# Cyllene.net
KiCad netlist of a schematic drawn in EAGLE
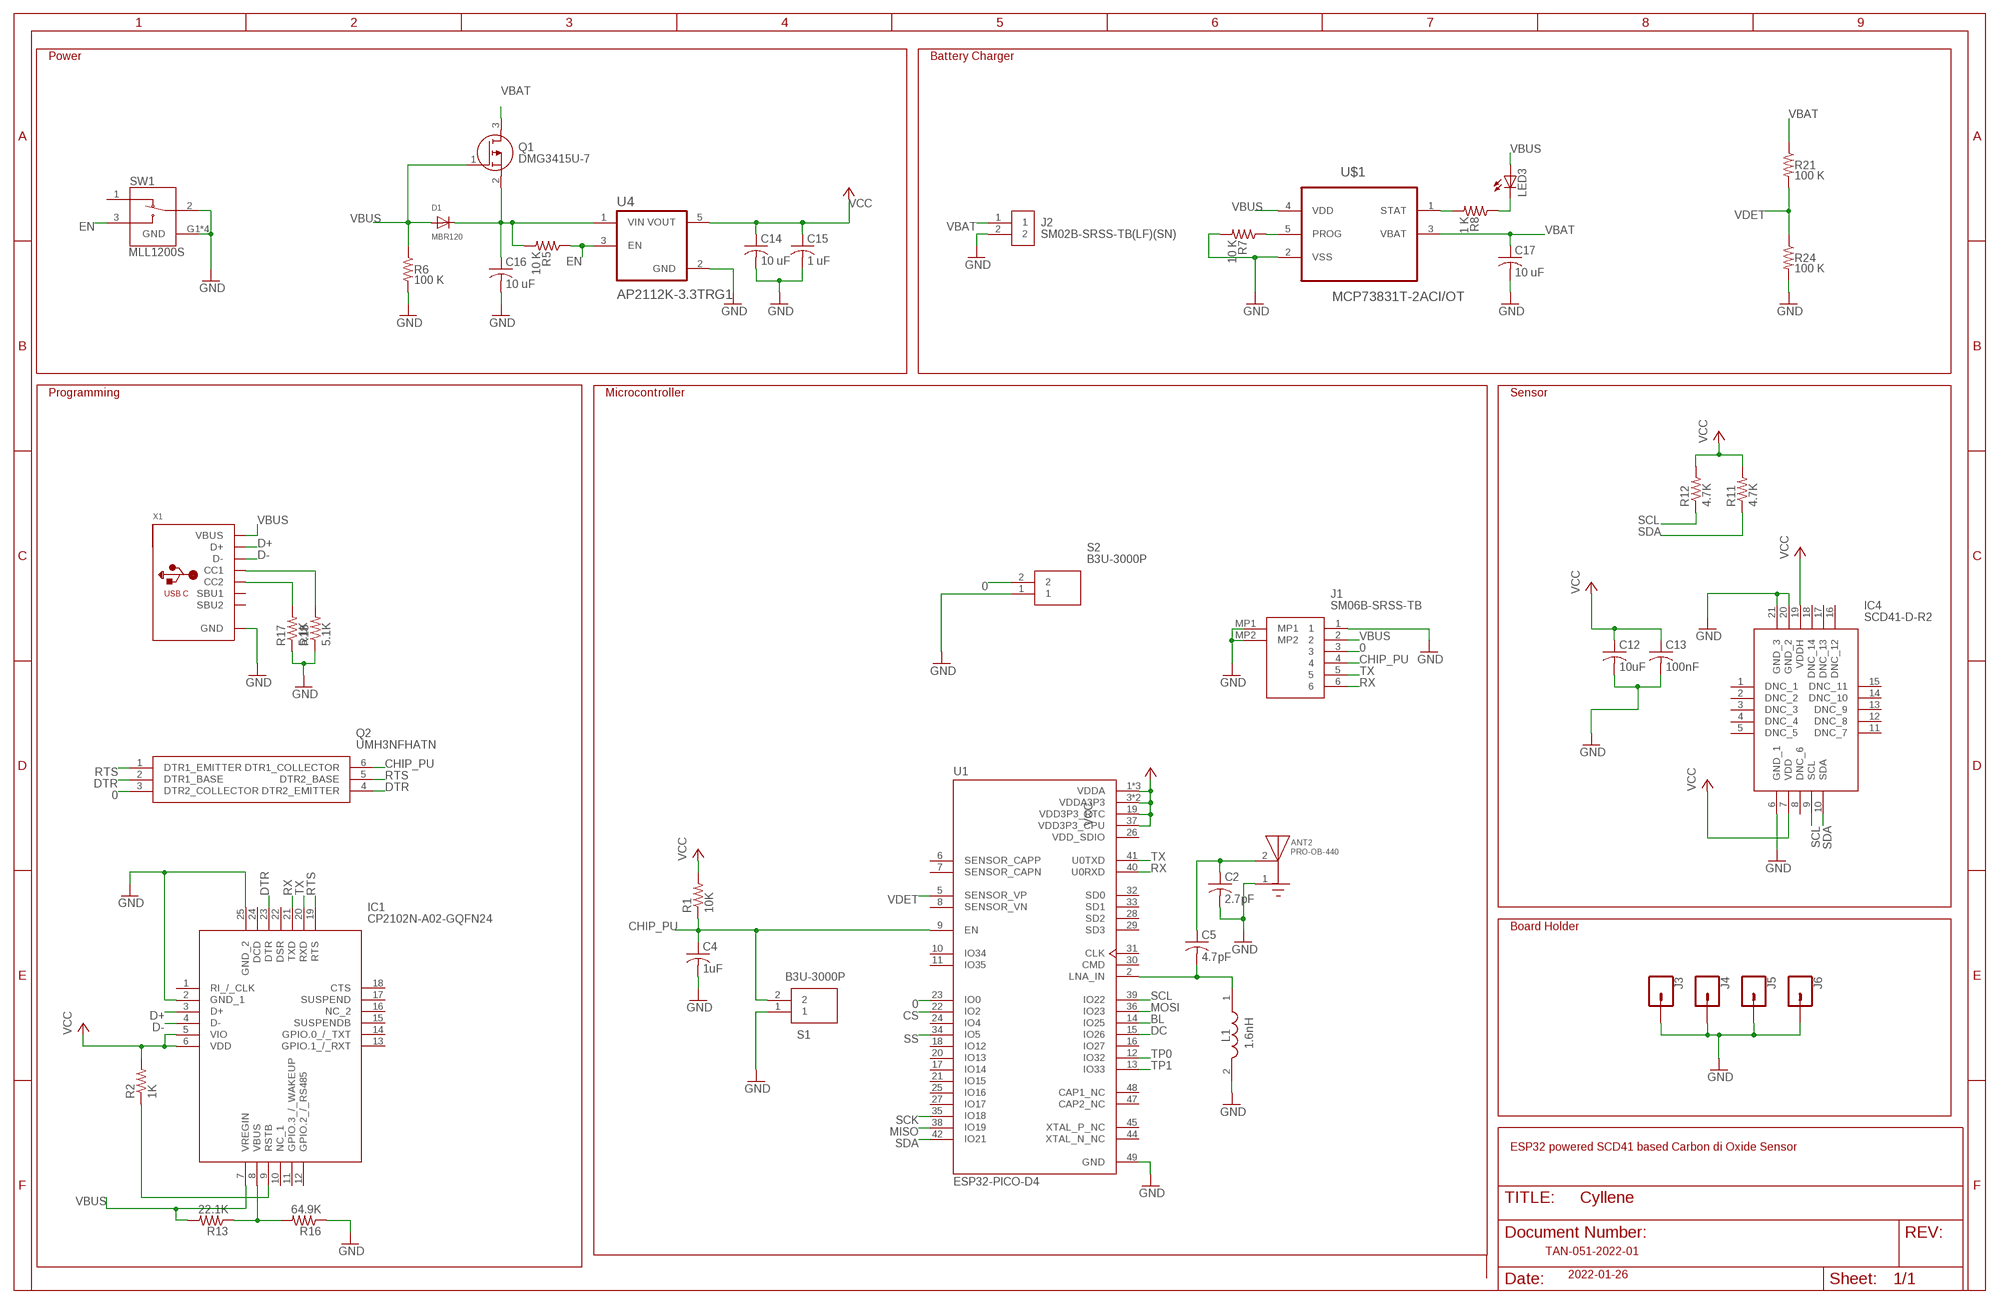
[diagram p0: schematic, sheet 1]

(export (version "E")
  (design (tool "Eeschema 10.0.6"))
  (components
    (comp (ref "ANT2")
      (value "PRO-OB-440")
      (footprint "eagle-import:ANT_PRO-OB-440")
      (fields (field (name "MF") "Proant AB"))
      (libsource (lib "eagle-import") (part "PRO-OB-440"))
    )
    (comp (ref "C2")
      (value "2.7pF")
      (footprint "eagle-import:C0402")
      (libsource (lib "eagle-import") (part "C-USC0402"))
    )
    (comp (ref "C4")
      (value "1uF")
      (footprint "eagle-import:C0402")
      (libsource (lib "eagle-import") (part "C-USC0402"))
    )
    (comp (ref "C5")
      (value "4.7pF")
      (footprint "eagle-import:C0402")
      (libsource (lib "eagle-import") (part "C-USC0402"))
    )
    (comp (ref "C12")
      (value "10uF")
      (footprint "eagle-import:C0402")
      (libsource (lib "eagle-import") (part "C-USC0402"))
    )
    (comp (ref "C13")
      (value "100nF")
      (footprint "eagle-import:C0402")
      (libsource (lib "eagle-import") (part "C-USC0402"))
    )
    (comp (ref "C14")
      (value "10 uF")
      (footprint "eagle-import:C0402")
      (libsource (lib "eagle-import") (part "C-USC0402"))
    )
    (comp (ref "C15")
      (value "1 uF")
      (footprint "eagle-import:C0402")
      (libsource (lib "eagle-import") (part "C-USC0402"))
    )
    (comp (ref "C16")
      (value "10 uF")
      (footprint "eagle-import:C0402")
      (libsource (lib "eagle-import") (part "C-USC0402"))
    )
    (comp (ref "C17")
      (value "10 uF")
      (footprint "eagle-import:C0402")
      (libsource (lib "eagle-import") (part "C-USC0402"))
    )
    (comp (ref "D1")
      (value "MBR120")
      (footprint "eagle-import:SOD-123")
      (libsource (lib "eagle-import") (part "DIODESOD-123"))
    )
    (comp (ref "IC1")
      (value "CP2102N-A02-GQFN24")
      (footprint "eagle-import:QFN50P400X400X80-25N")
      (fields (field (name "MOUSER_PART_NUMBER") "634-CP2102NA02GQFN24"))
      (libsource (lib "eagle-import") (part "CP2102N-A02-GQFN24"))
    )
    (comp (ref "IC4")
      (value "SCD41-D-R2")
      (footprint "eagle-import:SCD41DR2")
      (fields (field (name "MOUSER_PART_NUMBER") "403-SCD41-D-R2"))
      (libsource (lib "eagle-import") (part "SCD41-D-R2"))
    )
    (comp (ref "J1")
      (value "SM06B-SRSS-TB")
      (footprint "eagle-import:SM06BSRSSTB")
      (libsource (lib "eagle-import") (part "SM06B-SRSS-TB"))
    )
    (comp (ref "J2")
      (value "SM02B-SRSS-TB(LF)(SN)")
      (footprint "eagle-import:SM02B-SRSS-TB(LF)(SN)")
      (fields (field (name "MF") "JST Sales"))
      (libsource (lib "eagle-import") (part "SM02B-SRSS-TB(LF)(SN)"))
    )
    (comp (ref "J3")
      (value "CONN_01PTH_2MM")
      (footprint "eagle-import:1X01_2MM")
      (libsource (lib "eagle-import") (part "CONN_01PTH_2MM"))
    )
    (comp (ref "J4")
      (value "CONN_01PTH_2MM")
      (footprint "eagle-import:1X01_2MM")
      (libsource (lib "eagle-import") (part "CONN_01PTH_2MM"))
    )
    (comp (ref "J5")
      (value "CONN_01PTH_2MM")
      (footprint "eagle-import:1X01_2MM")
      (libsource (lib "eagle-import") (part "CONN_01PTH_2MM"))
    )
    (comp (ref "J6")
      (value "CONN_01PTH_2MM")
      (footprint "eagle-import:1X01_2MM")
      (libsource (lib "eagle-import") (part "CONN_01PTH_2MM"))
    )
    (comp (ref "L1")
      (value "1.6nH")
      (footprint "eagle-import:LQW15CNR20J00B")
      (fields
        (field (name "MANUFACTURER_PART_NUMBER") "LQG15WZ1N6C02D")
        (field (name "MOUSER_PART_NUMBER") "81-LQG15WZ1N6C02D")
      )
      (libsource (lib "eagle-import") (part "LQG15WZ1N6C02D"))
    )
    (comp (ref "LED3")
      (value "LEDCHIPLED_0603")
      (footprint "eagle-import:CHIPLED_0603")
      (libsource (lib "eagle-import") (part "LEDCHIPLED_0603"))
    )
    (comp (ref "Q1")
      (value "DMG3415U-7")
      (footprint "eagle-import:SOT96P240X100-3N")
      (fields (field (name "LCSC_PART_NUMBER") "C96616"))
      (libsource (lib "eagle-import") (part "DMG3415U-7"))
    )
    (comp (ref "Q2")
      (value "UMH3NFHATN")
      (footprint "eagle-import:SOT65P210X100-6N")
      (fields (field (name "MOUSER_PART_NUMBER") "755-UMH3NFHATN"))
      (libsource (lib "eagle-import") (part "UMH3NFHATN"))
    )
    (comp (ref "R1")
      (value "10K")
      (footprint "eagle-import:R0402")
      (libsource (lib "eagle-import") (part "R-US_R0402"))
    )
    (comp (ref "R2")
      (value "1K")
      (footprint "eagle-import:R0402")
      (libsource (lib "eagle-import") (part "R-US_R0402"))
    )
    (comp (ref "R5")
      (value "10 K")
      (footprint "eagle-import:R0402")
      (libsource (lib "eagle-import") (part "R-US_R0402"))
    )
    (comp (ref "R6")
      (value "100 K")
      (footprint "eagle-import:R0402")
      (libsource (lib "eagle-import") (part "R-US_R0402"))
    )
    (comp (ref "R7")
      (value "10 K")
      (footprint "eagle-import:R0402")
      (libsource (lib "eagle-import") (part "R-US_R0402"))
    )
    (comp (ref "R8")
      (value "1 K")
      (footprint "eagle-import:R0402")
      (libsource (lib "eagle-import") (part "R-US_R0402"))
    )
    (comp (ref "R11")
      (value "4.7K")
      (footprint "eagle-import:R0402")
      (libsource (lib "eagle-import") (part "R-US_R0402"))
    )
    (comp (ref "R12")
      (value "4.7K")
      (footprint "eagle-import:R0402")
      (libsource (lib "eagle-import") (part "R-US_R0402"))
    )
    (comp (ref "R13")
      (value "22.1K")
      (footprint "eagle-import:R0402")
      (libsource (lib "eagle-import") (part "R-US_R0402"))
    )
    (comp (ref "R16")
      (value "64.9K")
      (footprint "eagle-import:R0402")
      (libsource (lib "eagle-import") (part "R-US_R0402"))
    )
    (comp (ref "R17")
      (value "5.1K")
      (footprint "eagle-import:R0402")
      (libsource (lib "eagle-import") (part "R-US_R0402"))
    )
    (comp (ref "R18")
      (value "5.1K")
      (footprint "eagle-import:R0402")
      (libsource (lib "eagle-import") (part "R-US_R0402"))
    )
    (comp (ref "R21")
      (value "100 K")
      (footprint "eagle-import:R0402")
      (libsource (lib "eagle-import") (part "R-US_R0402"))
    )
    (comp (ref "R24")
      (value "100 K")
      (footprint "eagle-import:R0402")
      (libsource (lib "eagle-import") (part "R-US_R0402"))
    )
    (comp (ref "S1")
      (value "B3U-3000P")
      (footprint "eagle-import:B3U-1000P")
      (fields (field (name "MOUSER_PART_NUMBER") "653-B3U-3000P"))
      (libsource (lib "eagle-import") (part "B3U-3000P"))
    )
    (comp (ref "S2")
      (value "B3U-3000P")
      (footprint "eagle-import:B3U-1000P")
      (fields (field (name "MOUSER_PART_NUMBER") "653-B3U-3000P"))
      (libsource (lib "eagle-import") (part "B3U-3000P"))
    )
    (comp (ref "SW1")
      (value "MLL1200S")
      (footprint "eagle-import:SW_MLL1200S")
      (fields (field (name "COMMENT") "1437575-1") (field (name "MF") "TE Connectivity"))
      (libsource (lib "eagle-import") (part "MLL1200S"))
    )
    (comp (ref "U$1")
      (value "MCP73831T-2ACI/OT")
      (footprint "eagle-import:SOT95P280X145-5N")
      (fields (field (name "MF") "Microchip"))
      (libsource (lib "eagle-import") (part "MCP73831T-2ACI/OT"))
    )
    (comp (ref "U1")
      (value "ESP32-PICO-D4")
      (footprint "eagle-import:PQFN50P700X700X104-49N")
      (fields (field (name "MF") "Espressif Systems"))
      (libsource (lib "eagle-import") (part "ESP32-PICO-D4"))
    )
    (comp (ref "U4")
      (value "AP2112K-3.3TRG1")
      (footprint "eagle-import:SOT95P285X140-5N")
      (fields (field (name "MF") "Diodes Inc."))
      (libsource (lib "eagle-import") (part "AP2112K-3.3TRG1"))
    )
    (comp (ref "X1")
      (value "MICROBUILDER_USB_C")
      (footprint "eagle-import:MICROBUILDER_USB_C_CUSB31-CFM2AX-01-X")
      (libsource (lib "eagle-import") (part "MICROBUILDER_USB_C"))
    )
  )
  (nets
    (net (code "1") (name "/0") (class "Default")
      (node (ref "J1") (pin "3") (pinfunction "3_3") (pintype "bidirectional"))
      (node (ref "Q2") (pin "3") (pinfunction "DTR2_COLLECTOR_3") (pintype "bidirectional"))
      (node (ref "S2") (pin "2") (pinfunction "2_2") (pintype "bidirectional"))
      (node (ref "U1") (pin "23") (pinfunction "IO0_23") (pintype "bidirectional"))
    )
    (net (code "2") (name "/BL") (class "Default")
      (node (ref "U1") (pin "14") (pinfunction "IO25_14") (pintype "bidirectional"))
    )
    (net (code "3") (name "/CHIP_PU") (class "Default")
      (node (ref "C4") (pin "1") (pinfunction "1_1") (pintype "passive"))
      (node (ref "J1") (pin "4") (pinfunction "4_4") (pintype "bidirectional"))
      (node (ref "Q2") (pin "6") (pinfunction "DTR1_COLLECTOR_6") (pintype "bidirectional"))
      (node (ref "R1") (pin "1") (pinfunction "1_1") (pintype "passive"))
      (node (ref "S1") (pin "2") (pinfunction "2_2") (pintype "bidirectional"))
      (node (ref "U1") (pin "9") (pinfunction "EN_9") (pintype "input"))
    )
    (net (code "4") (name "/CS") (class "Default")
      (node (ref "U1") (pin "22") (pinfunction "IO2_22") (pintype "bidirectional"))
    )
    (net (code "5") (name "/D+") (class "Default")
      (node (ref "IC1") (pin "3") (pinfunction "D+_3") (pintype "bidirectional"))
      (node (ref "X1") (pin "A6") (pinfunction "D+_A6") (pintype "bidirectional"))
      (node (ref "X1") (pin "B6") (pinfunction "D+_B6") (pintype "bidirectional"))
    )
    (net (code "6") (name "/D-") (class "Default")
      (node (ref "IC1") (pin "4") (pinfunction "D-_4") (pintype "bidirectional"))
      (node (ref "X1") (pin "A7") (pinfunction "D-_A7") (pintype "bidirectional"))
      (node (ref "X1") (pin "B7") (pinfunction "D-_B7") (pintype "bidirectional"))
    )
    (net (code "7") (name "/DC") (class "Default")
      (node (ref "U1") (pin "15") (pinfunction "IO26_15") (pintype "bidirectional"))
    )
    (net (code "8") (name "/DTR") (class "Default")
      (node (ref "IC1") (pin "23") (pinfunction "DTR_23") (pintype "bidirectional"))
      (node (ref "Q2") (pin "2") (pinfunction "DTR1_BASE_2") (pintype "bidirectional"))
      (node (ref "Q2") (pin "4") (pinfunction "DTR2_EMITTER_4") (pintype "bidirectional"))
    )
    (net (code "9") (name "/EN") (class "Default")
      (node (ref "R5") (pin "1") (pinfunction "1_1") (pintype "passive"))
      (node (ref "SW1") (pin "3") (pinfunction "3_3") (pintype "passive"))
      (node (ref "U4") (pin "3") (pinfunction "EN_3") (pintype "input"))
    )
    (net (code "10") (name "/MISO") (class "Default")
      (node (ref "U1") (pin "38") (pinfunction "IO19_38") (pintype "bidirectional"))
    )
    (net (code "11") (name "/MOSI") (class "Default")
      (node (ref "U1") (pin "36") (pinfunction "IO23_36") (pintype "bidirectional"))
    )
    (net (code "12") (name "/RTS") (class "Default")
      (node (ref "IC1") (pin "19") (pinfunction "RTS_19") (pintype "bidirectional"))
      (node (ref "Q2") (pin "1") (pinfunction "DTR1_EMITTER_1") (pintype "bidirectional"))
      (node (ref "Q2") (pin "5") (pinfunction "DTR2_BASE_5") (pintype "bidirectional"))
    )
    (net (code "13") (name "/RX") (class "Default")
      (node (ref "IC1") (pin "21") (pinfunction "TXD_21") (pintype "bidirectional"))
      (node (ref "J1") (pin "6") (pinfunction "6_6") (pintype "bidirectional"))
      (node (ref "U1") (pin "40") (pinfunction "U0RXD_40") (pintype "bidirectional"))
    )
    (net (code "14") (name "/SCK") (class "Default")
      (node (ref "U1") (pin "35") (pinfunction "IO18_35") (pintype "bidirectional"))
    )
    (net (code "15") (name "/SCL") (class "Default")
      (node (ref "IC4") (pin "9") (pinfunction "SCL_9") (pintype "bidirectional"))
      (node (ref "R12") (pin "1") (pinfunction "1_1") (pintype "passive"))
      (node (ref "U1") (pin "39") (pinfunction "IO22_39") (pintype "bidirectional"))
    )
    (net (code "16") (name "/SDA") (class "Default")
      (node (ref "IC4") (pin "10") (pinfunction "SDA_10") (pintype "bidirectional"))
      (node (ref "R11") (pin "1") (pinfunction "1_1") (pintype "passive"))
      (node (ref "U1") (pin "42") (pinfunction "IO21_42") (pintype "bidirectional"))
    )
    (net (code "17") (name "/SS") (class "Default")
      (node (ref "U1") (pin "34") (pinfunction "IO5_34") (pintype "bidirectional"))
    )
    (net (code "18") (name "/TP0") (class "Default")
      (node (ref "U1") (pin "12") (pinfunction "IO32_12") (pintype "bidirectional"))
    )
    (net (code "19") (name "/TP1") (class "Default")
      (node (ref "U1") (pin "13") (pinfunction "IO33_13") (pintype "bidirectional"))
    )
    (net (code "20") (name "/TX") (class "Default")
      (node (ref "IC1") (pin "20") (pinfunction "RXD_20") (pintype "bidirectional"))
      (node (ref "J1") (pin "5") (pinfunction "5_5") (pintype "bidirectional"))
      (node (ref "U1") (pin "41") (pinfunction "U0TXD_41") (pintype "bidirectional"))
    )
    (net (code "21") (name "/VBAT") (class "Default")
      (node (ref "C17") (pin "1") (pinfunction "1_1") (pintype "passive"))
      (node (ref "J2") (pin "1") (pinfunction "1_1") (pintype "bidirectional"))
      (node (ref "Q1") (pin "3") (pinfunction "D_3") (pintype "bidirectional"))
      (node (ref "R21") (pin "1") (pinfunction "1_1") (pintype "passive"))
      (node (ref "U$1") (pin "3") (pinfunction "VBAT_3") (pintype "output"))
    )
    (net (code "22") (name "/VBUS") (class "Default")
      (node (ref "D1") (pin "A") (pinfunction "A_A") (pintype "passive"))
      (node (ref "IC1") (pin "7") (pinfunction "VREGIN_7") (pintype "bidirectional"))
      (node (ref "J1") (pin "2") (pinfunction "2_2") (pintype "bidirectional"))
      (node (ref "LED3") (pin "A") (pinfunction "A_A") (pintype "passive"))
      (node (ref "Q1") (pin "1") (pinfunction "G_1") (pintype "bidirectional"))
      (node (ref "R13") (pin "2") (pinfunction "2_2") (pintype "passive"))
      (node (ref "R6") (pin "1") (pinfunction "1_1") (pintype "passive"))
      (node (ref "U$1") (pin "4") (pinfunction "VDD_4") (pintype "power_in"))
      (node (ref "X1") (pin "A4B9") (pinfunction "VBUS_A4B9") (pintype "power_in"))
      (node (ref "X1") (pin "B4A9") (pinfunction "VBUS_B4A9") (pintype "power_in"))
    )
    (net (code "23") (name "/VDD_SDIO") (class "Default")
      (node (ref "U1") (pin "26") (pinfunction "VDD_SDIO_26") (pintype "power_in"))
    )
    (net (code "24") (name "/VDET") (class "Default")
      (node (ref "R21") (pin "2") (pinfunction "2_2") (pintype "passive"))
      (node (ref "R24") (pin "1") (pinfunction "1_1") (pintype "passive"))
      (node (ref "U1") (pin "5") (pinfunction "SENSOR_VP_5") (pintype "input"))
    )
    (net (code "25") (name "GND") (class "Default")
      (node (ref "ANT2") (pin "1") (pinfunction "GND_1") (pintype "power_in"))
      (node (ref "C12") (pin "2") (pinfunction "2_2") (pintype "passive"))
      (node (ref "C13") (pin "2") (pinfunction "2_2") (pintype "passive"))
      (node (ref "C14") (pin "2") (pinfunction "2_2") (pintype "passive"))
      (node (ref "C15") (pin "2") (pinfunction "2_2") (pintype "passive"))
      (node (ref "C16") (pin "2") (pinfunction "2_2") (pintype "passive"))
      (node (ref "C17") (pin "2") (pinfunction "2_2") (pintype "passive"))
      (node (ref "C2") (pin "2") (pinfunction "2_2") (pintype "passive"))
      (node (ref "C4") (pin "2") (pinfunction "2_2") (pintype "passive"))
      (node (ref "IC1") (pin "2") (pinfunction "GND_1_2") (pintype "bidirectional"))
      (node (ref "IC1") (pin "25") (pinfunction "GND_2_25") (pintype "bidirectional"))
      (node (ref "IC4") (pin "20") (pinfunction "GND_2_20") (pintype "bidirectional"))
      (node (ref "IC4") (pin "21") (pinfunction "GND_3_21") (pintype "bidirectional"))
      (node (ref "IC4") (pin "6") (pinfunction "GND_1_6") (pintype "bidirectional"))
      (node (ref "J1") (pin "1") (pinfunction "1_1") (pintype "bidirectional"))
      (node (ref "J1") (pin "MP1") (pinfunction "MP1_MP1") (pintype "bidirectional"))
      (node (ref "J1") (pin "MP2") (pinfunction "MP2_MP2") (pintype "bidirectional"))
      (node (ref "J2") (pin "2") (pinfunction "2_2") (pintype "bidirectional"))
      (node (ref "J3") (pin "1") (pinfunction "1_1") (pintype "passive"))
      (node (ref "J4") (pin "1") (pinfunction "1_1") (pintype "passive"))
      (node (ref "J5") (pin "1") (pinfunction "1_1") (pintype "passive"))
      (node (ref "J6") (pin "1") (pinfunction "1_1") (pintype "passive"))
      (node (ref "L1") (pin "2") (pinfunction "2_2") (pintype "bidirectional"))
      (node (ref "R16") (pin "1") (pinfunction "1_1") (pintype "passive"))
      (node (ref "R17") (pin "1") (pinfunction "1_1") (pintype "passive"))
      (node (ref "R18") (pin "1") (pinfunction "1_1") (pintype "passive"))
      (node (ref "R24") (pin "2") (pinfunction "2_2") (pintype "passive"))
      (node (ref "R6") (pin "2") (pinfunction "2_2") (pintype "passive"))
      (node (ref "R7") (pin "2") (pinfunction "2_2") (pintype "passive"))
      (node (ref "S1") (pin "1") (pinfunction "1_1") (pintype "bidirectional"))
      (node (ref "S2") (pin "1") (pinfunction "1_1") (pintype "bidirectional"))
      (node (ref "SW1") (pin "2") (pinfunction "2_2") (pintype "passive"))
      (node (ref "SW1") (pin "G1") (pinfunction "GND_G1") (pintype "power_in"))
      (node (ref "SW1") (pin "G2") (pinfunction "GND_G2") (pintype "power_in"))
      (node (ref "SW1") (pin "G3") (pinfunction "GND_G3") (pintype "power_in"))
      (node (ref "SW1") (pin "G4") (pinfunction "GND_G4") (pintype "power_in"))
      (node (ref "U$1") (pin "2") (pinfunction "VSS_2") (pintype "power_in"))
      (node (ref "U1") (pin "49") (pinfunction "GND_49") (pintype "power_in"))
      (node (ref "U4") (pin "2") (pinfunction "GND_2") (pintype "power_in"))
      (node (ref "X1") (pin "A1B12") (pinfunction "GND_A1B12") (pintype "power_in"))
      (node (ref "X1") (pin "B1A12") (pinfunction "GND_B1A12") (pintype "power_in"))
    )
    (net (code "26") (name "Net-(ANT2-FEED)") (class "Default")
      (node (ref "ANT2") (pin "2") (pinfunction "FEED_2") (pintype "input"))
      (node (ref "C2") (pin "1") (pinfunction "1_1") (pintype "passive"))
      (node (ref "C5") (pin "1") (pinfunction "1_1") (pintype "passive"))
    )
    (net (code "27") (name "Net-(IC1-RSTB)") (class "Default")
      (node (ref "IC1") (pin "9") (pinfunction "RSTB_9") (pintype "bidirectional"))
      (node (ref "R2") (pin "1") (pinfunction "1_1") (pintype "passive"))
    )
    (net (code "28") (name "Net-(IC1-VBUS)") (class "Default")
      (node (ref "IC1") (pin "8") (pinfunction "VBUS_8") (pintype "bidirectional"))
      (node (ref "R13") (pin "1") (pinfunction "1_1") (pintype "passive"))
      (node (ref "R16") (pin "2") (pinfunction "2_2") (pintype "passive"))
    )
    (net (code "29") (name "Net-(LED3-PadC)") (class "Default")
      (node (ref "LED3") (pin "C") (pinfunction "C_C") (pintype "passive"))
      (node (ref "R8") (pin "1") (pinfunction "1_1") (pintype "passive"))
    )
    (net (code "30") (name "Net-(Q1-S)") (class "Default")
      (node (ref "C16") (pin "1") (pinfunction "1_1") (pintype "passive"))
      (node (ref "D1") (pin "C") (pinfunction "C_C") (pintype "passive"))
      (node (ref "Q1") (pin "2") (pinfunction "S_2") (pintype "bidirectional"))
      (node (ref "R5") (pin "2") (pinfunction "2_2") (pintype "passive"))
      (node (ref "U4") (pin "1") (pinfunction "VIN_1") (pintype "power_in"))
    )
    (net (code "31") (name "Net-(U$1-PROG)") (class "Default")
      (node (ref "R7") (pin "1") (pinfunction "1_1") (pintype "passive"))
      (node (ref "U$1") (pin "5") (pinfunction "PROG_5") (pintype "input"))
    )
    (net (code "32") (name "Net-(U$1-STAT)") (class "Default")
      (node (ref "R8") (pin "2") (pinfunction "2_2") (pintype "passive"))
      (node (ref "U$1") (pin "1") (pinfunction "STAT_1") (pintype "output"))
    )
    (net (code "33") (name "Net-(U1-LNA_IN)") (class "Default")
      (node (ref "C5") (pin "2") (pinfunction "2_2") (pintype "passive"))
      (node (ref "L1") (pin "1") (pinfunction "1_1") (pintype "bidirectional"))
      (node (ref "U1") (pin "2") (pinfunction "LNA_IN_2") (pintype "bidirectional"))
    )
    (net (code "34") (name "Net-(X1-CC1)") (class "Default")
      (node (ref "R18") (pin "2") (pinfunction "2_2") (pintype "passive"))
      (node (ref "X1") (pin "A5") (pinfunction "CC1_A5") (pintype "bidirectional"))
    )
    (net (code "35") (name "Net-(X1-CC2)") (class "Default")
      (node (ref "R17") (pin "2") (pinfunction "2_2") (pintype "passive"))
      (node (ref "X1") (pin "B5") (pinfunction "CC2_B5") (pintype "bidirectional"))
    )
    (net (code "36") (name "VCC") (class "Default")
      (node (ref "C12") (pin "1") (pinfunction "1_1") (pintype "passive"))
      (node (ref "C13") (pin "1") (pinfunction "1_1") (pintype "passive"))
      (node (ref "C14") (pin "1") (pinfunction "1_1") (pintype "passive"))
      (node (ref "C15") (pin "1") (pinfunction "1_1") (pintype "passive"))
      (node (ref "IC1") (pin "5") (pinfunction "VIO_5") (pintype "bidirectional"))
      (node (ref "IC1") (pin "6") (pinfunction "VDD_6") (pintype "bidirectional"))
      (node (ref "IC4") (pin "19") (pinfunction "VDDH_19") (pintype "bidirectional"))
      (node (ref "IC4") (pin "7") (pinfunction "VDD_7") (pintype "bidirectional"))
      (node (ref "R1") (pin "2") (pinfunction "2_2") (pintype "passive"))
      (node (ref "R11") (pin "2") (pinfunction "2_2") (pintype "passive"))
      (node (ref "R12") (pin "2") (pinfunction "2_2") (pintype "passive"))
      (node (ref "R2") (pin "2") (pinfunction "2_2") (pintype "passive"))
      (node (ref "U1") (pin "1") (pinfunction "VDDA_1") (pintype "power_in"))
      (node (ref "U1") (pin "19") (pinfunction "VDD3P3_RTC_19") (pintype "power_in"))
      (node (ref "U1") (pin "3") (pinfunction "VDDA3P3_3") (pintype "power_in"))
      (node (ref "U1") (pin "37") (pinfunction "VDD3P3_CPU_37") (pintype "power_in"))
      (node (ref "U1") (pin "4") (pinfunction "VDDA3P3_4") (pintype "power_in"))
      (node (ref "U1") (pin "43") (pinfunction "VDDA_43") (pintype "power_in"))
      (node (ref "U1") (pin "46") (pinfunction "VDDA_46") (pintype "power_in"))
      (node (ref "U4") (pin "5") (pinfunction "VOUT_5") (pintype "power_in"))
    )
    (net (code "37") (name "unconnected-(IC1-CTS-Pad18)") (class "Default")
      (node (ref "IC1") (pin "18") (pinfunction "CTS_18") (pintype "bidirectional"))
    )
    (net (code "38") (name "unconnected-(IC1-DCD-Pad24)") (class "Default")
      (node (ref "IC1") (pin "24") (pinfunction "DCD_24") (pintype "bidirectional"))
    )
    (net (code "39") (name "unconnected-(IC1-DSR-Pad22)") (class "Default")
      (node (ref "IC1") (pin "22") (pinfunction "DSR_22") (pintype "bidirectional"))
    )
    (net (code "40") (name "unconnected-(IC1-GPIO.0_{slash}_TXT-Pad14)") (class "Default")
      (node (ref "IC1") (pin "14") (pinfunction "GPIO.0_/_TXT_14") (pintype "bidirectional"))
    )
    (net (code "41") (name "unconnected-(IC1-GPIO.1_{slash}_RXT-Pad13)") (class "Default")
      (node (ref "IC1") (pin "13") (pinfunction "GPIO.1_/_RXT_13") (pintype "bidirectional"))
    )
    (net (code "42") (name "unconnected-(IC1-GPIO.2_{slash}_RS485-Pad12)") (class "Default")
      (node (ref "IC1") (pin "12") (pinfunction "GPIO.2_/_RS485_12") (pintype "bidirectional"))
    )
    (net (code "43") (name "unconnected-(IC1-GPIO.3_{slash}_WAKEUP-Pad11)") (class "Default")
      (node (ref "IC1") (pin "11") (pinfunction "GPIO.3_/_WAKEUP_11") (pintype "bidirectional"))
    )
    (net (code "44") (name "unconnected-(IC1-NC_1-Pad10)") (class "Default")
      (node (ref "IC1") (pin "10") (pinfunction "NC_1_10") (pintype "bidirectional"))
    )
    (net (code "45") (name "unconnected-(IC1-NC_2-Pad16)") (class "Default")
      (node (ref "IC1") (pin "16") (pinfunction "NC_2_16") (pintype "bidirectional"))
    )
    (net (code "46") (name "unconnected-(IC1-RI_{slash}_CLK-Pad1)") (class "Default")
      (node (ref "IC1") (pin "1") (pinfunction "RI_/_CLK_1") (pintype "bidirectional"))
    )
    (net (code "47") (name "unconnected-(IC1-SUSPEND-Pad17)") (class "Default")
      (node (ref "IC1") (pin "17") (pinfunction "SUSPEND_17") (pintype "bidirectional"))
    )
    (net (code "48") (name "unconnected-(IC1-SUSPENDB-Pad15)") (class "Default")
      (node (ref "IC1") (pin "15") (pinfunction "SUSPENDB_15") (pintype "bidirectional"))
    )
    (net (code "49") (name "unconnected-(IC4-DNC_1-Pad1)") (class "Default")
      (node (ref "IC4") (pin "1") (pinfunction "DNC_1_1") (pintype "bidirectional"))
    )
    (net (code "50") (name "unconnected-(IC4-DNC_2-Pad2)") (class "Default")
      (node (ref "IC4") (pin "2") (pinfunction "DNC_2_2") (pintype "bidirectional"))
    )
    (net (code "51") (name "unconnected-(IC4-DNC_3-Pad3)") (class "Default")
      (node (ref "IC4") (pin "3") (pinfunction "DNC_3_3") (pintype "bidirectional"))
    )
    (net (code "52") (name "unconnected-(IC4-DNC_4-Pad4)") (class "Default")
      (node (ref "IC4") (pin "4") (pinfunction "DNC_4_4") (pintype "bidirectional"))
    )
    (net (code "53") (name "unconnected-(IC4-DNC_5-Pad5)") (class "Default")
      (node (ref "IC4") (pin "5") (pinfunction "DNC_5_5") (pintype "bidirectional"))
    )
    (net (code "54") (name "unconnected-(IC4-DNC_6-Pad8)") (class "Default")
      (node (ref "IC4") (pin "8") (pinfunction "DNC_6_8") (pintype "bidirectional"))
    )
    (net (code "55") (name "unconnected-(IC4-DNC_7-Pad11)") (class "Default")
      (node (ref "IC4") (pin "11") (pinfunction "DNC_7_11") (pintype "bidirectional"))
    )
    (net (code "56") (name "unconnected-(IC4-DNC_8-Pad12)") (class "Default")
      (node (ref "IC4") (pin "12") (pinfunction "DNC_8_12") (pintype "bidirectional"))
    )
    (net (code "57") (name "unconnected-(IC4-DNC_9-Pad13)") (class "Default")
      (node (ref "IC4") (pin "13") (pinfunction "DNC_9_13") (pintype "bidirectional"))
    )
    (net (code "58") (name "unconnected-(IC4-DNC_10-Pad14)") (class "Default")
      (node (ref "IC4") (pin "14") (pinfunction "DNC_10_14") (pintype "bidirectional"))
    )
    (net (code "59") (name "unconnected-(IC4-DNC_11-Pad15)") (class "Default")
      (node (ref "IC4") (pin "15") (pinfunction "DNC_11_15") (pintype "bidirectional"))
    )
    (net (code "60") (name "unconnected-(IC4-DNC_12-Pad16)") (class "Default")
      (node (ref "IC4") (pin "16") (pinfunction "DNC_12_16") (pintype "bidirectional"))
    )
    (net (code "61") (name "unconnected-(IC4-DNC_13-Pad17)") (class "Default")
      (node (ref "IC4") (pin "17") (pinfunction "DNC_13_17") (pintype "bidirectional"))
    )
    (net (code "62") (name "unconnected-(IC4-DNC_14-Pad18)") (class "Default")
      (node (ref "IC4") (pin "18") (pinfunction "DNC_14_18") (pintype "bidirectional"))
    )
    (net (code "63") (name "unconnected-(SW1-Pad1)") (class "Default")
      (node (ref "SW1") (pin "1") (pinfunction "1_1") (pintype "passive"))
    )
    (net (code "64") (name "unconnected-(U1-CAP1_NC-Pad48)") (class "Default")
      (node (ref "U1") (pin "48") (pinfunction "CAP1_NC_48") (pintype "no_connect"))
    )
    (net (code "65") (name "unconnected-(U1-CAP2_NC-Pad47)") (class "Default")
      (node (ref "U1") (pin "47") (pinfunction "CAP2_NC_47") (pintype "no_connect"))
    )
    (net (code "66") (name "unconnected-(U1-CLK-Pad31)") (class "Default")
      (node (ref "U1") (pin "31") (pinfunction "CLK_31") (pintype "bidirectional"))
    )
    (net (code "67") (name "unconnected-(U1-CMD-Pad30)") (class "Default")
      (node (ref "U1") (pin "30") (pinfunction "CMD_30") (pintype "bidirectional"))
    )
    (net (code "68") (name "unconnected-(U1-IO4-Pad24)") (class "Default")
      (node (ref "U1") (pin "24") (pinfunction "IO4_24") (pintype "bidirectional"))
    )
    (net (code "69") (name "unconnected-(U1-IO12-Pad18)") (class "Default")
      (node (ref "U1") (pin "18") (pinfunction "IO12_18") (pintype "bidirectional"))
    )
    (net (code "70") (name "unconnected-(U1-IO13-Pad20)") (class "Default")
      (node (ref "U1") (pin "20") (pinfunction "IO13_20") (pintype "bidirectional"))
    )
    (net (code "71") (name "unconnected-(U1-IO14-Pad17)") (class "Default")
      (node (ref "U1") (pin "17") (pinfunction "IO14_17") (pintype "bidirectional"))
    )
    (net (code "72") (name "unconnected-(U1-IO15-Pad21)") (class "Default")
      (node (ref "U1") (pin "21") (pinfunction "IO15_21") (pintype "bidirectional"))
    )
    (net (code "73") (name "unconnected-(U1-IO16-Pad25)") (class "Default")
      (node (ref "U1") (pin "25") (pinfunction "IO16_25") (pintype "bidirectional"))
    )
    (net (code "74") (name "unconnected-(U1-IO17-Pad27)") (class "Default")
      (node (ref "U1") (pin "27") (pinfunction "IO17_27") (pintype "bidirectional"))
    )
    (net (code "75") (name "unconnected-(U1-IO27-Pad16)") (class "Default")
      (node (ref "U1") (pin "16") (pinfunction "IO27_16") (pintype "bidirectional"))
    )
    (net (code "76") (name "unconnected-(U1-IO34-Pad10)") (class "Default")
      (node (ref "U1") (pin "10") (pinfunction "IO34_10") (pintype "input"))
    )
    (net (code "77") (name "unconnected-(U1-IO35-Pad11)") (class "Default")
      (node (ref "U1") (pin "11") (pinfunction "IO35_11") (pintype "input"))
    )
    (net (code "78") (name "unconnected-(U1-SD0-Pad32)") (class "Default")
      (node (ref "U1") (pin "32") (pinfunction "SD0_32") (pintype "bidirectional"))
    )
    (net (code "79") (name "unconnected-(U1-SD1-Pad33)") (class "Default")
      (node (ref "U1") (pin "33") (pinfunction "SD1_33") (pintype "bidirectional"))
    )
    (net (code "80") (name "unconnected-(U1-SD2-Pad28)") (class "Default")
      (node (ref "U1") (pin "28") (pinfunction "SD2_28") (pintype "bidirectional"))
    )
    (net (code "81") (name "unconnected-(U1-SD3-Pad29)") (class "Default")
      (node (ref "U1") (pin "29") (pinfunction "SD3_29") (pintype "bidirectional"))
    )
    (net (code "82") (name "unconnected-(U1-SENSOR_CAPN-Pad7)") (class "Default")
      (node (ref "U1") (pin "7") (pinfunction "SENSOR_CAPN_7") (pintype "input"))
    )
    (net (code "83") (name "unconnected-(U1-SENSOR_CAPP-Pad6)") (class "Default")
      (node (ref "U1") (pin "6") (pinfunction "SENSOR_CAPP_6") (pintype "input"))
    )
    (net (code "84") (name "unconnected-(U1-SENSOR_VN-Pad8)") (class "Default")
      (node (ref "U1") (pin "8") (pinfunction "SENSOR_VN_8") (pintype "input"))
    )
    (net (code "85") (name "unconnected-(U1-XTAL_N_NC-Pad44)") (class "Default")
      (node (ref "U1") (pin "44") (pinfunction "XTAL_N_NC_44") (pintype "no_connect"))
    )
    (net (code "86") (name "unconnected-(U1-XTAL_P_NC-Pad45)") (class "Default")
      (node (ref "U1") (pin "45") (pinfunction "XTAL_P_NC_45") (pintype "no_connect"))
    )
    (net (code "87") (name "unconnected-(X1-SBU1-PadA8)") (class "Default")
      (node (ref "X1") (pin "A8") (pinfunction "SBU1_A8") (pintype "bidirectional"))
    )
    (net (code "88") (name "unconnected-(X1-SBU2-PadB8)") (class "Default")
      (node (ref "X1") (pin "B8") (pinfunction "SBU2_B8") (pintype "bidirectional"))
    )
  )
)
